# XTX.net
KiCad netlist of a schematic drawn in Altium Designer
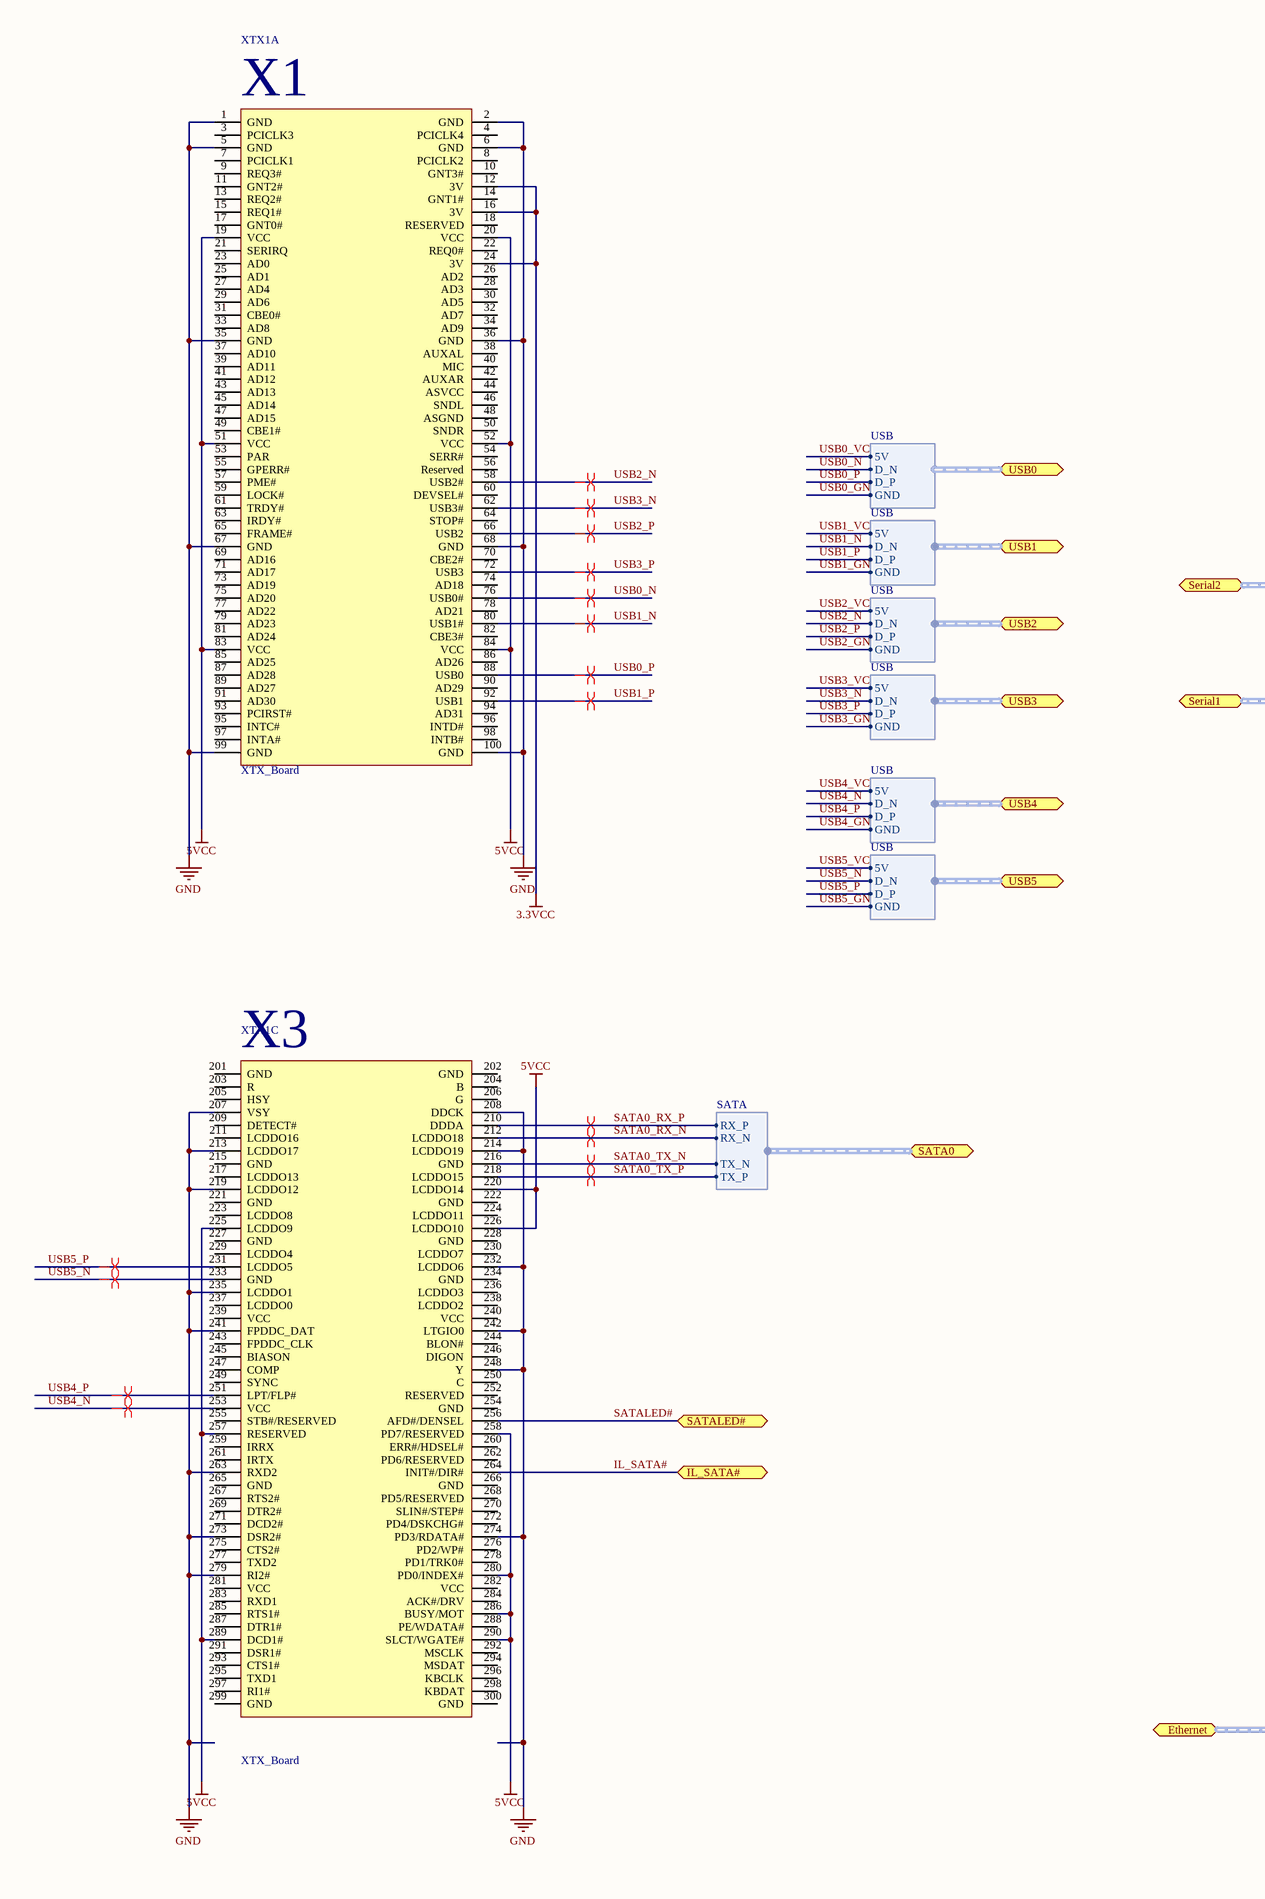
[diagram p0: XTX.SchDoc, left]
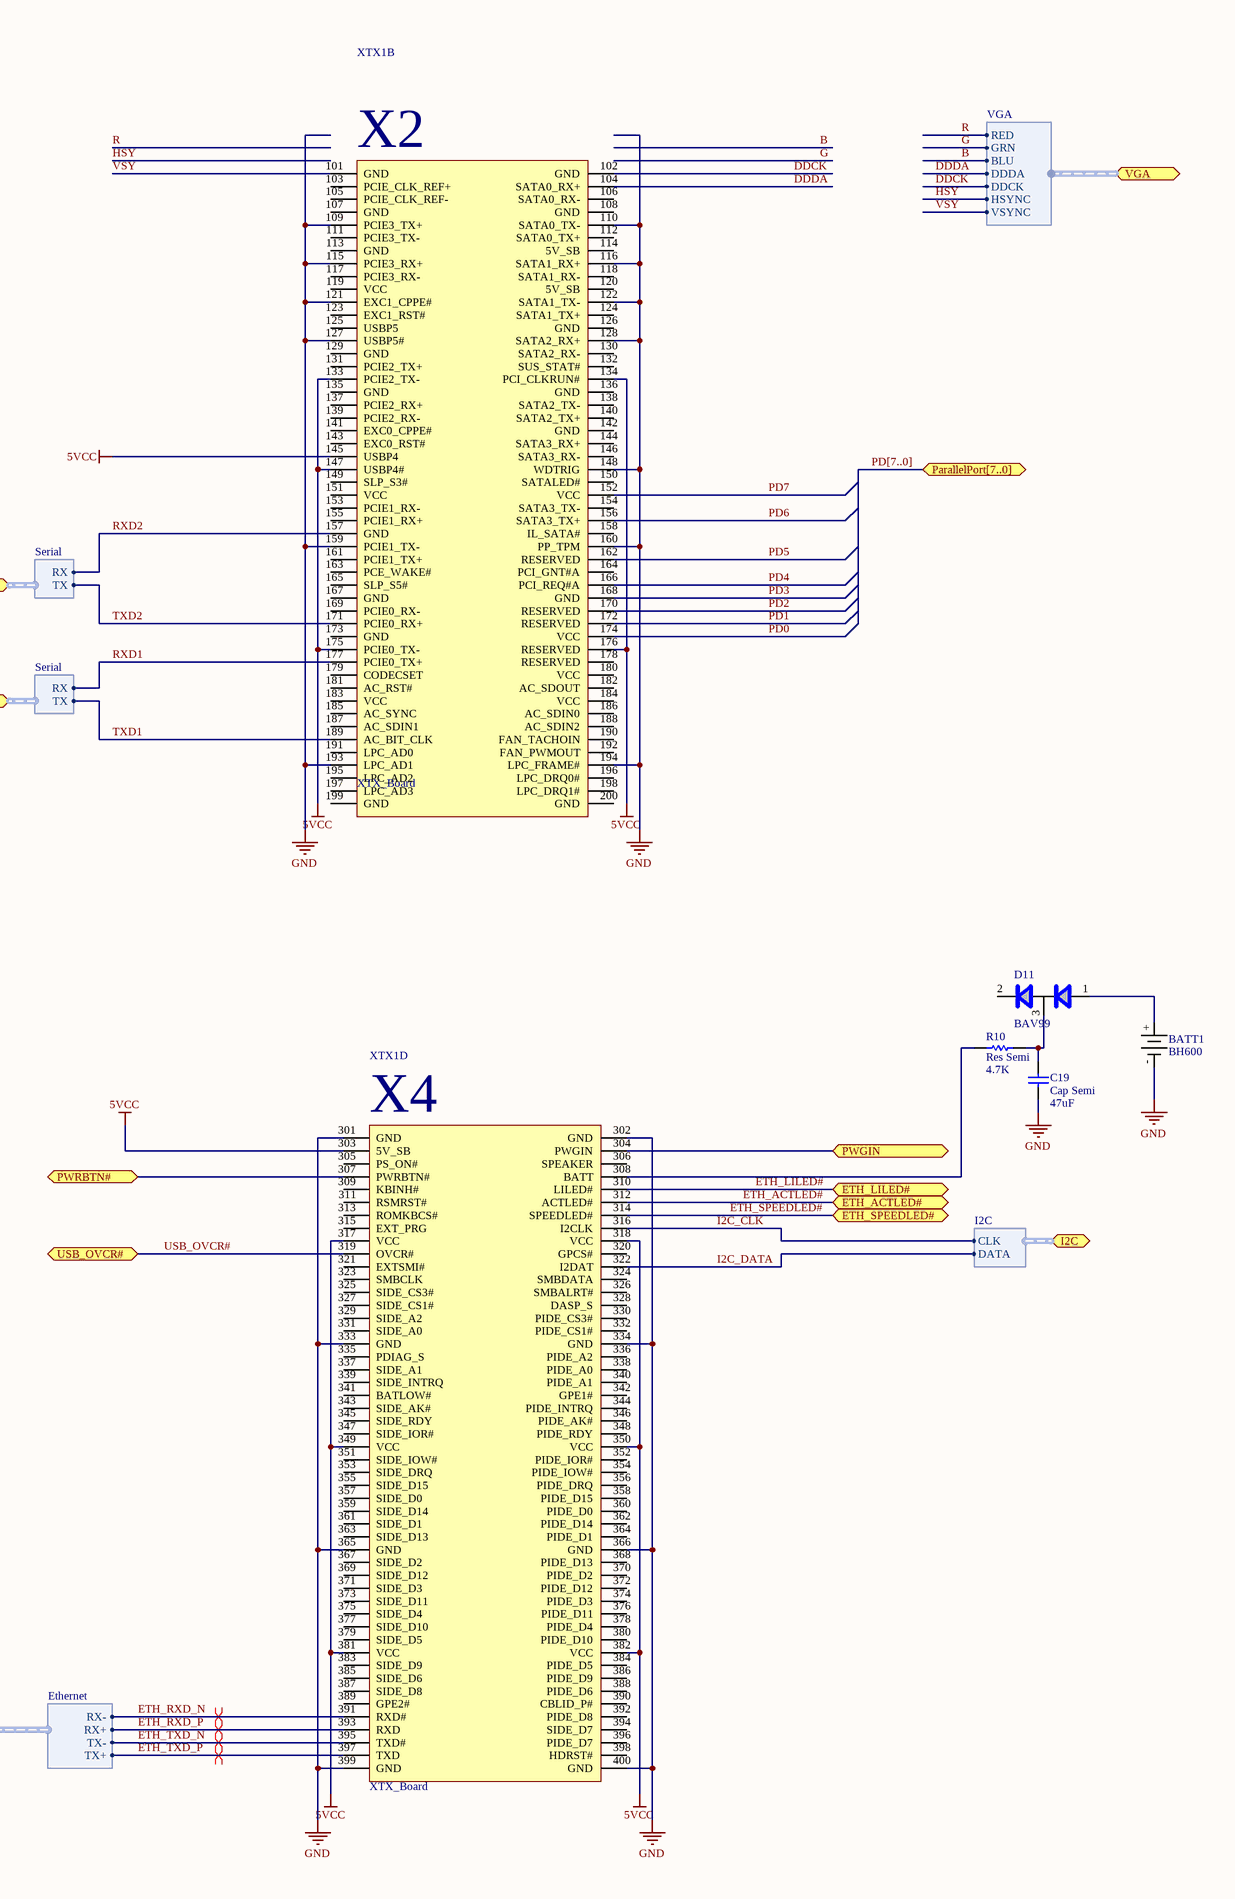
[diagram p1: XTX.SchDoc, right]

(export (version "E")
  (design (tool "Eeschema 10.0.6"))
  (components
    (comp (ref "BATT1")
      (value "BH600")
      (footprint "MemoryProtectionDevices:BH600")
      (description "16mm Battery Holder - Memory Protection Devices")
      (libsource (lib "CoinBatteryHolders") (part "BH600"))
    )
    (comp (ref "C19")
      (value "Cap Semi")
      (footprint "C1210")
      (description "Capacitor (Semiconductor SIM Model)")
      (fields (field (name "ALTIUM_VALUE") "47uF") (field (name "PUBLISHER") "Altium Limited"))
      (libsource (lib "Miscellaneous Devices") (part "Cap Semi"))
    )
    (comp (ref "D11")
      (value "BAV99")
      (footprint "SOT-23")
      (description "Dual Surface Mount Switching Diode")
      (fields (field (name "DIGIKEY PART NUMBER") "BAV99-FDICT-ND"))
      (libsource (lib "Diodes") (part "BAV99"))
    )
    (comp (ref "R10")
      (value "Res Semi")
      (footprint "1005[0402]")
      (description "Semiconductor Resistor")
      (fields (field (name "ALTIUM_VALUE") "4.7K") (field (name "PUBLISHER") "Altium Limited"))
      (libsource (lib "Miscellaneous Devices") (part "Res Semi"))
    )
    (comp (ref "XTX1") (value "XTX_Board") (footprint "XTX_Board") (libsource (lib "XTX") (part "XTX_Board")))
  )
  (nets
    (net (code "8") (name "/DDCK") (class "Default")
      (node (ref "XTX1") (pin "102") (pinfunction "GND_102") (pintype "passive"))
    )
    (net (code "9") (name "/DDDA") (class "Default")
      (node (ref "XTX1") (pin "104") (pinfunction "SATA0_RX+_104") (pintype "passive"))
    )
    (net (code "10") (name "/ETH_ACTLED#") (class "Default")
      (node (ref "XTX1") (pin "312") (pinfunction "ACTLED#_312") (pintype "passive"))
    )
    (net (code "11") (name "/ETH_LILED#") (class "Default")
      (node (ref "XTX1") (pin "310") (pinfunction "LILED#_310") (pintype "passive"))
    )
    (net (code "12") (name "/ETH_RXD_N") (class "Default")
      (node (ref "XTX1") (pin "391") (pinfunction "RXD#_391") (pintype "passive"))
    )
    (net (code "13") (name "/ETH_RXD_P") (class "Default")
      (node (ref "XTX1") (pin "393") (pinfunction "RXD_393") (pintype "passive"))
    )
    (net (code "14") (name "/ETH_SPEEDLED#") (class "Default")
      (node (ref "XTX1") (pin "314") (pinfunction "SPEEDLED#_314") (pintype "passive"))
    )
    (net (code "15") (name "/ETH_TXD_N") (class "Default")
      (node (ref "XTX1") (pin "395") (pinfunction "TXD#_395") (pintype "passive"))
    )
    (net (code "16") (name "/ETH_TXD_P") (class "Default")
      (node (ref "XTX1") (pin "397") (pinfunction "TXD_397") (pintype "passive"))
    )
    (net (code "19") (name "/I2C_CLK") (class "Default")
      (node (ref "XTX1") (pin "316") (pinfunction "I2CLK_316") (pintype "passive"))
    )
    (net (code "20") (name "/I2C_DATA") (class "Default")
      (node (ref "XTX1") (pin "322") (pinfunction "I2DAT_322") (pintype "passive"))
    )
    (net (code "21") (name "/IL_SATA#") (class "Default")
      (node (ref "XTX1") (pin "264") (pinfunction "INIT#/DIR#_264") (pintype "passive"))
    )
    (net (code "22") (name "/PD0") (class "Default")
      (node (ref "XTX1") (pin "174") (pinfunction "VCC_174") (pintype "passive"))
    )
    (net (code "23") (name "/PD1") (class "Default")
      (node (ref "XTX1") (pin "172") (pinfunction "RESERVED_172") (pintype "passive"))
    )
    (net (code "24") (name "/PD2") (class "Default")
      (node (ref "XTX1") (pin "170") (pinfunction "RESERVED_170") (pintype "passive"))
    )
    (net (code "25") (name "/PD3") (class "Default")
      (node (ref "XTX1") (pin "168") (pinfunction "GND_168") (pintype "passive"))
    )
    (net (code "26") (name "/PD4") (class "Default")
      (node (ref "XTX1") (pin "166") (pinfunction "PCI_REQ#A_166") (pintype "passive"))
    )
    (net (code "27") (name "/PD5") (class "Default")
      (node (ref "XTX1") (pin "162") (pinfunction "RESERVED_162") (pintype "passive"))
    )
    (net (code "28") (name "/PD6") (class "Default")
      (node (ref "XTX1") (pin "156") (pinfunction "SATA3_TX+_156") (pintype "passive"))
    )
    (net (code "29") (name "/PD7") (class "Default")
      (node (ref "XTX1") (pin "152") (pinfunction "VCC_152") (pintype "passive"))
    )
    (net (code "31") (name "/PWGIN") (class "Default")
      (node (ref "XTX1") (pin "304") (pinfunction "PWGIN_304") (pintype "passive"))
    )
    (net (code "32") (name "/PWRBTN#") (class "Default")
      (node (ref "XTX1") (pin "307") (pinfunction "PWRBTN#_307") (pintype "passive"))
    )
    (net (code "34") (name "/RXD1") (class "Default")
      (node (ref "XTX1") (pin "177") (pinfunction "PCIE0_TX+_177") (pintype "passive"))
    )
    (net (code "35") (name "/RXD2") (class "Default")
      (node (ref "XTX1") (pin "157") (pinfunction "GND_157") (pintype "passive"))
    )
    (net (code "36") (name "/SATA0_RX_N") (class "Default")
      (node (ref "XTX1") (pin "212") (pinfunction "LCDDO18_212") (pintype "passive"))
    )
    (net (code "37") (name "/SATA0_RX_P") (class "Default")
      (node (ref "XTX1") (pin "210") (pinfunction "DDDA_210") (pintype "passive"))
    )
    (net (code "38") (name "/SATA0_TX_N") (class "Default")
      (node (ref "XTX1") (pin "216") (pinfunction "GND_216") (pintype "passive"))
    )
    (net (code "39") (name "/SATA0_TX_P") (class "Default")
      (node (ref "XTX1") (pin "218") (pinfunction "LCDDO15_218") (pintype "passive"))
    )
    (net (code "40") (name "/SATALED#") (class "Default")
      (node (ref "XTX1") (pin "256") (pinfunction "AFD#/DENSEL_256") (pintype "passive"))
    )
    (net (code "41") (name "/TXD1") (class "Default")
      (node (ref "XTX1") (pin "189") (pinfunction "AC_BIT_CLK_189") (pintype "passive"))
    )
    (net (code "42") (name "/TXD2") (class "Default")
      (node (ref "XTX1") (pin "171") (pinfunction "PCIE0_RX+_171") (pintype "passive"))
    )
    (net (code "44") (name "/USB0_N") (class "Default")
      (node (ref "XTX1") (pin "76") (pinfunction "USB0#_76") (pintype "passive"))
    )
    (net (code "45") (name "/USB0_P") (class "Default")
      (node (ref "XTX1") (pin "88") (pinfunction "USB0_88") (pintype "passive"))
    )
    (net (code "48") (name "/USB1_N") (class "Default")
      (node (ref "XTX1") (pin "80") (pinfunction "USB1#_80") (pintype "passive"))
    )
    (net (code "49") (name "/USB1_P") (class "Default")
      (node (ref "XTX1") (pin "92") (pinfunction "USB1_92") (pintype "passive"))
    )
    (net (code "52") (name "/USB2_N") (class "Default")
      (node (ref "XTX1") (pin "58") (pinfunction "USB2#_58") (pintype "passive"))
    )
    (net (code "53") (name "/USB2_P") (class "Default")
      (node (ref "XTX1") (pin "66") (pinfunction "USB2_66") (pintype "passive"))
    )
    (net (code "56") (name "/USB3_N") (class "Default")
      (node (ref "XTX1") (pin "62") (pinfunction "USB3#_62") (pintype "passive"))
    )
    (net (code "57") (name "/USB3_P") (class "Default")
      (node (ref "XTX1") (pin "72") (pinfunction "USB3_72") (pintype "passive"))
    )
    (net (code "60") (name "/USB4_N") (class "Default")
      (node (ref "XTX1") (pin "253") (pinfunction "VCC_253") (pintype "passive"))
    )
    (net (code "61") (name "/USB4_P") (class "Default")
      (node (ref "XTX1") (pin "251") (pinfunction "LPT/FLP#_251") (pintype "passive"))
    )
    (net (code "64") (name "/USB5_N") (class "Default")
      (node (ref "XTX1") (pin "233") (pinfunction "GND_233") (pintype "passive"))
    )
    (net (code "65") (name "/USB5_P") (class "Default")
      (node (ref "XTX1") (pin "231") (pinfunction "LCDDO5_231") (pintype "passive"))
    )
    (net (code "67") (name "/USB_OVCR#") (class "Default")
      (node (ref "XTX1") (pin "319") (pinfunction "OVCR#_319") (pintype "passive"))
    )
    (net (code "68") (name "/VSY") (class "Default")
      (node (ref "XTX1") (pin "101") (pinfunction "GND_101") (pintype "passive"))
    )
    (net (code "75") (name "3.3VCC") (class "Default")
      (node (ref "XTX1") (pin "12") (pinfunction "3V_12") (pintype "passive"))
      (node (ref "XTX1") (pin "16") (pinfunction "3V_16") (pintype "passive"))
      (node (ref "XTX1") (pin "24") (pinfunction "3V_24") (pintype "passive"))
    )
    (net (code "76") (name "5VCC") (class "Default")
      (node (ref "XTX1") (pin "133") (pinfunction "PCIE2_TX-_133") (pintype "passive"))
      (node (ref "XTX1") (pin "134") (pinfunction "PCI_CLKRUN#_134") (pintype "passive"))
      (node (ref "XTX1") (pin "145") (pinfunction "USBP4_145") (pintype "passive"))
      (node (ref "XTX1") (pin "147") (pinfunction "USBP4#_147") (pintype "passive"))
      (node (ref "XTX1") (pin "175") (pinfunction "PCIE0_TX-_175") (pintype "passive"))
      (node (ref "XTX1") (pin "176") (pinfunction "RESERVED_176") (pintype "passive"))
      (node (ref "XTX1") (pin "19") (pinfunction "VCC_19") (pintype "passive"))
      (node (ref "XTX1") (pin "20") (pinfunction "VCC_20") (pintype "passive"))
      (node (ref "XTX1") (pin "220") (pinfunction "LCDDO14_220") (pintype "passive"))
      (node (ref "XTX1") (pin "225") (pinfunction "LCDDO9_225") (pintype "passive"))
      (node (ref "XTX1") (pin "226") (pinfunction "LCDDO10_226") (pintype "passive"))
      (node (ref "XTX1") (pin "257") (pinfunction "RESERVED_257") (pintype "passive"))
      (node (ref "XTX1") (pin "258") (pinfunction "PD7/RESERVED_258") (pintype "passive"))
      (node (ref "XTX1") (pin "280") (pinfunction "PD0/INDEX#_280") (pintype "passive"))
      (node (ref "XTX1") (pin "286") (pinfunction "BUSY/MOT_286") (pintype "passive"))
      (node (ref "XTX1") (pin "289") (pinfunction "DCD1#_289") (pintype "passive"))
      (node (ref "XTX1") (pin "290") (pinfunction "SLCT/WGATE#_290") (pintype "passive"))
      (node (ref "XTX1") (pin "303") (pinfunction "5V_SB_303") (pintype "passive"))
      (node (ref "XTX1") (pin "317") (pinfunction "VCC_317") (pintype "passive"))
      (node (ref "XTX1") (pin "318") (pinfunction "VCC_318") (pintype "passive"))
      (node (ref "XTX1") (pin "349") (pinfunction "VCC_349") (pintype "passive"))
      (node (ref "XTX1") (pin "350") (pinfunction "VCC_350") (pintype "passive"))
      (node (ref "XTX1") (pin "381") (pinfunction "VCC_381") (pintype "passive"))
      (node (ref "XTX1") (pin "382") (pinfunction "VCC_382") (pintype "passive"))
      (node (ref "XTX1") (pin "51") (pinfunction "VCC_51") (pintype "passive"))
      (node (ref "XTX1") (pin "52") (pinfunction "VCC_52") (pintype "passive"))
      (node (ref "XTX1") (pin "83") (pinfunction "VCC_83") (pintype "passive"))
      (node (ref "XTX1") (pin "84") (pinfunction "VCC_84") (pintype "passive"))
    )
    (net (code "77") (name "GND") (class "Default")
      (node (ref "BATT1") (pin "-") (pinfunction "1_-") (pintype "passive"))
      (node (ref "C19") (pin "1") (pinfunction "1_1") (pintype "passive"))
      (node (ref "XTX1") (pin "1") (pinfunction "GND_1") (pintype "passive"))
      (node (ref "XTX1") (pin "100") (pinfunction "GND_100") (pintype "passive"))
      (node (ref "XTX1") (pin "109") (pinfunction "PCIE3_TX+_109") (pintype "passive"))
      (node (ref "XTX1") (pin "110") (pinfunction "SATA0_TX-_110") (pintype "passive"))
      (node (ref "XTX1") (pin "115") (pinfunction "PCIE3_RX+_115") (pintype "passive"))
      (node (ref "XTX1") (pin "116") (pinfunction "SATA1_RX+_116") (pintype "passive"))
      (node (ref "XTX1") (pin "121") (pinfunction "EXC1_CPPE#_121") (pintype "passive"))
      (node (ref "XTX1") (pin "122") (pinfunction "SATA1_TX-_122") (pintype "passive"))
      (node (ref "XTX1") (pin "127") (pinfunction "USBP5#_127") (pintype "passive"))
      (node (ref "XTX1") (pin "128") (pinfunction "SATA2_RX+_128") (pintype "passive"))
      (node (ref "XTX1") (pin "148") (pinfunction "WDTRIG_148") (pintype "passive"))
      (node (ref "XTX1") (pin "159") (pinfunction "PCIE1_TX-_159") (pintype "passive"))
      (node (ref "XTX1") (pin "160") (pinfunction "PP_TPM_160") (pintype "passive"))
      (node (ref "XTX1") (pin "193") (pinfunction "LPC_AD1_193") (pintype "passive"))
      (node (ref "XTX1") (pin "194") (pinfunction "LPC_FRAME#_194") (pintype "passive"))
      (node (ref "XTX1") (pin "2") (pinfunction "GND_2") (pintype "passive"))
      (node (ref "XTX1") (pin "207") (pinfunction "VSY_207") (pintype "passive"))
      (node (ref "XTX1") (pin "208") (pinfunction "DDCK_208") (pintype "passive"))
      (node (ref "XTX1") (pin "213") (pinfunction "LCDDO17_213") (pintype "passive"))
      (node (ref "XTX1") (pin "214") (pinfunction "LCDDO19_214") (pintype "passive"))
      (node (ref "XTX1") (pin "219") (pinfunction "LCDDO12_219") (pintype "passive"))
      (node (ref "XTX1") (pin "232") (pinfunction "LCDDO6_232") (pintype "passive"))
      (node (ref "XTX1") (pin "235") (pinfunction "LCDDO1_235") (pintype "passive"))
      (node (ref "XTX1") (pin "241") (pinfunction "FPDDC_DAT_241") (pintype "passive"))
      (node (ref "XTX1") (pin "242") (pinfunction "LTGIO0_242") (pintype "passive"))
      (node (ref "XTX1") (pin "248") (pinfunction "Y_248") (pintype "passive"))
      (node (ref "XTX1") (pin "263") (pinfunction "RXD2_263") (pintype "passive"))
      (node (ref "XTX1") (pin "273") (pinfunction "DSR2#_273") (pintype "passive"))
      (node (ref "XTX1") (pin "274") (pinfunction "PD3/RDATA#_274") (pintype "passive"))
      (node (ref "XTX1") (pin "279") (pinfunction "RI2#_279") (pintype "passive"))
      (node (ref "XTX1") (pin "301") (pinfunction "GND_301") (pintype "passive"))
      (node (ref "XTX1") (pin "302") (pinfunction "GND_302") (pintype "passive"))
      (node (ref "XTX1") (pin "333") (pinfunction "GND_333") (pintype "passive"))
      (node (ref "XTX1") (pin "334") (pinfunction "GND_334") (pintype "passive"))
      (node (ref "XTX1") (pin "35") (pinfunction "GND_35") (pintype "passive"))
      (node (ref "XTX1") (pin "36") (pinfunction "GND_36") (pintype "passive"))
      (node (ref "XTX1") (pin "365") (pinfunction "GND_365") (pintype "passive"))
      (node (ref "XTX1") (pin "366") (pinfunction "GND_366") (pintype "passive"))
      (node (ref "XTX1") (pin "399") (pinfunction "GND_399") (pintype "passive"))
      (node (ref "XTX1") (pin "400") (pinfunction "GND_400") (pintype "passive"))
      (node (ref "XTX1") (pin "5") (pinfunction "GND_5") (pintype "passive"))
      (node (ref "XTX1") (pin "6") (pinfunction "GND_6") (pintype "passive"))
      (node (ref "XTX1") (pin "67") (pinfunction "GND_67") (pintype "passive"))
      (node (ref "XTX1") (pin "68") (pinfunction "GND_68") (pintype "passive"))
      (node (ref "XTX1") (pin "99") (pinfunction "GND_99") (pintype "passive"))
    )
    (net (code "78") (name "Net-(BATT1-0)") (class "Default")
      (node (ref "BATT1") (pin "+") (pinfunction "0_+") (pintype "passive"))
      (node (ref "D11") (pin "1") (pinfunction "1_1") (pintype "passive"))
    )
    (net (code "79") (name "Net-(C19-Pad2)") (class "Default")
      (node (ref "C19") (pin "2") (pinfunction "2_2") (pintype "passive"))
      (node (ref "D11") (pin "3") (pinfunction "3_3") (pintype "passive"))
      (node (ref "R10") (pin "2") (pinfunction "2_2") (pintype "passive"))
    )
    (net (code "80") (name "Net-(XTX1D-BATT)") (class "Default")
      (node (ref "R10") (pin "1") (pinfunction "1_1") (pintype "passive"))
      (node (ref "XTX1") (pin "308") (pinfunction "BATT_308") (pintype "passive"))
    )
    (net (code "81") (name "unconnected-(D11-Pad2)") (class "Default")
      (node (ref "D11") (pin "2") (pinfunction "2_2") (pintype "passive"))
    )
    (net (code "82") (name "unconnected-(XTX1A-AD0-Pad23)") (class "Default")
      (node (ref "XTX1") (pin "23") (pinfunction "AD0_23") (pintype "passive"))
    )
    (net (code "83") (name "unconnected-(XTX1A-AD1-Pad25)") (class "Default")
      (node (ref "XTX1") (pin "25") (pinfunction "AD1_25") (pintype "passive"))
    )
    (net (code "84") (name "unconnected-(XTX1A-AD2-Pad26)") (class "Default")
      (node (ref "XTX1") (pin "26") (pinfunction "AD2_26") (pintype "passive"))
    )
    (net (code "85") (name "unconnected-(XTX1A-AD3-Pad28)") (class "Default")
      (node (ref "XTX1") (pin "28") (pinfunction "AD3_28") (pintype "passive"))
    )
    (net (code "86") (name "unconnected-(XTX1A-AD4-Pad27)") (class "Default")
      (node (ref "XTX1") (pin "27") (pinfunction "AD4_27") (pintype "passive"))
    )
    (net (code "87") (name "unconnected-(XTX1A-AD5-Pad30)") (class "Default")
      (node (ref "XTX1") (pin "30") (pinfunction "AD5_30") (pintype "passive"))
    )
    (net (code "88") (name "unconnected-(XTX1A-AD6-Pad29)") (class "Default")
      (node (ref "XTX1") (pin "29") (pinfunction "AD6_29") (pintype "passive"))
    )
    (net (code "89") (name "unconnected-(XTX1A-AD7-Pad32)") (class "Default")
      (node (ref "XTX1") (pin "32") (pinfunction "AD7_32") (pintype "passive"))
    )
    (net (code "90") (name "unconnected-(XTX1A-AD8-Pad33)") (class "Default")
      (node (ref "XTX1") (pin "33") (pinfunction "AD8_33") (pintype "passive"))
    )
    (net (code "91") (name "unconnected-(XTX1A-AD9-Pad34)") (class "Default")
      (node (ref "XTX1") (pin "34") (pinfunction "AD9_34") (pintype "passive"))
    )
    (net (code "92") (name "unconnected-(XTX1A-AD10-Pad37)") (class "Default")
      (node (ref "XTX1") (pin "37") (pinfunction "AD10_37") (pintype "passive"))
    )
    (net (code "93") (name "unconnected-(XTX1A-AD11-Pad39)") (class "Default")
      (node (ref "XTX1") (pin "39") (pinfunction "AD11_39") (pintype "passive"))
    )
    (net (code "94") (name "unconnected-(XTX1A-AD12-Pad41)") (class "Default")
      (node (ref "XTX1") (pin "41") (pinfunction "AD12_41") (pintype "passive"))
    )
    (net (code "95") (name "unconnected-(XTX1A-AD13-Pad43)") (class "Default")
      (node (ref "XTX1") (pin "43") (pinfunction "AD13_43") (pintype "passive"))
    )
    (net (code "96") (name "unconnected-(XTX1A-AD14-Pad45)") (class "Default")
      (node (ref "XTX1") (pin "45") (pinfunction "AD14_45") (pintype "passive"))
    )
    (net (code "97") (name "unconnected-(XTX1A-AD15-Pad47)") (class "Default")
      (node (ref "XTX1") (pin "47") (pinfunction "AD15_47") (pintype "passive"))
    )
    (net (code "98") (name "unconnected-(XTX1A-AD16-Pad69)") (class "Default")
      (node (ref "XTX1") (pin "69") (pinfunction "AD16_69") (pintype "passive"))
    )
    (net (code "99") (name "unconnected-(XTX1A-AD17-Pad71)") (class "Default")
      (node (ref "XTX1") (pin "71") (pinfunction "AD17_71") (pintype "passive"))
    )
    (net (code "100") (name "unconnected-(XTX1A-AD18-Pad74)") (class "Default")
      (node (ref "XTX1") (pin "74") (pinfunction "AD18_74") (pintype "passive"))
    )
    (net (code "101") (name "unconnected-(XTX1A-AD19-Pad73)") (class "Default")
      (node (ref "XTX1") (pin "73") (pinfunction "AD19_73") (pintype "passive"))
    )
    (net (code "102") (name "unconnected-(XTX1A-AD20-Pad75)") (class "Default")
      (node (ref "XTX1") (pin "75") (pinfunction "AD20_75") (pintype "passive"))
    )
    (net (code "103") (name "unconnected-(XTX1A-AD21-Pad78)") (class "Default")
      (node (ref "XTX1") (pin "78") (pinfunction "AD21_78") (pintype "passive"))
    )
    (net (code "104") (name "unconnected-(XTX1A-AD22-Pad77)") (class "Default")
      (node (ref "XTX1") (pin "77") (pinfunction "AD22_77") (pintype "passive"))
    )
    (net (code "105") (name "unconnected-(XTX1A-AD23-Pad79)") (class "Default")
      (node (ref "XTX1") (pin "79") (pinfunction "AD23_79") (pintype "passive"))
    )
    (net (code "106") (name "unconnected-(XTX1A-AD24-Pad81)") (class "Default")
      (node (ref "XTX1") (pin "81") (pinfunction "AD24_81") (pintype "passive"))
    )
    (net (code "107") (name "unconnected-(XTX1A-AD25-Pad85)") (class "Default")
      (node (ref "XTX1") (pin "85") (pinfunction "AD25_85") (pintype "passive"))
    )
    (net (code "108") (name "unconnected-(XTX1A-AD26-Pad86)") (class "Default")
      (node (ref "XTX1") (pin "86") (pinfunction "AD26_86") (pintype "passive"))
    )
    (net (code "109") (name "unconnected-(XTX1A-AD27-Pad89)") (class "Default")
      (node (ref "XTX1") (pin "89") (pinfunction "AD27_89") (pintype "passive"))
    )
    (net (code "110") (name "unconnected-(XTX1A-AD28-Pad87)") (class "Default")
      (node (ref "XTX1") (pin "87") (pinfunction "AD28_87") (pintype "passive"))
    )
    (net (code "111") (name "unconnected-(XTX1A-AD29-Pad90)") (class "Default")
      (node (ref "XTX1") (pin "90") (pinfunction "AD29_90") (pintype "passive"))
    )
    (net (code "112") (name "unconnected-(XTX1A-AD30-Pad91)") (class "Default")
      (node (ref "XTX1") (pin "91") (pinfunction "AD30_91") (pintype "passive"))
    )
    (net (code "113") (name "unconnected-(XTX1A-AD31-Pad94)") (class "Default")
      (node (ref "XTX1") (pin "94") (pinfunction "AD31_94") (pintype "passive"))
    )
    (net (code "114") (name "unconnected-(XTX1A-ASGND-Pad48)") (class "Default")
      (node (ref "XTX1") (pin "48") (pinfunction "ASGND_48") (pintype "passive"))
    )
    (net (code "115") (name "unconnected-(XTX1A-ASVCC-Pad44)") (class "Default")
      (node (ref "XTX1") (pin "44") (pinfunction "ASVCC_44") (pintype "passive"))
    )
    (net (code "116") (name "unconnected-(XTX1A-AUXAL-Pad38)") (class "Default")
      (node (ref "XTX1") (pin "38") (pinfunction "AUXAL_38") (pintype "passive"))
    )
    (net (code "117") (name "unconnected-(XTX1A-AUXAR-Pad42)") (class "Default")
      (node (ref "XTX1") (pin "42") (pinfunction "AUXAR_42") (pintype "passive"))
    )
    (net (code "118") (name "unconnected-(XTX1A-CBE0#-Pad31)") (class "Default")
      (node (ref "XTX1") (pin "31") (pinfunction "CBE0#_31") (pintype "passive"))
    )
    (net (code "119") (name "unconnected-(XTX1A-CBE1#-Pad49)") (class "Default")
      (node (ref "XTX1") (pin "49") (pinfunction "CBE1#_49") (pintype "passive"))
    )
    (net (code "120") (name "unconnected-(XTX1A-CBE2#-Pad70)") (class "Default")
      (node (ref "XTX1") (pin "70") (pinfunction "CBE2#_70") (pintype "passive"))
    )
    (net (code "121") (name "unconnected-(XTX1A-CBE3#-Pad82)") (class "Default")
      (node (ref "XTX1") (pin "82") (pinfunction "CBE3#_82") (pintype "passive"))
    )
    (net (code "122") (name "unconnected-(XTX1A-DEVSEL#-Pad60)") (class "Default")
      (node (ref "XTX1") (pin "60") (pinfunction "DEVSEL#_60") (pintype "passive"))
    )
    (net (code "123") (name "unconnected-(XTX1A-FRAME#-Pad65)") (class "Default")
      (node (ref "XTX1") (pin "65") (pinfunction "FRAME#_65") (pintype "passive"))
    )
    (net (code "124") (name "unconnected-(XTX1A-GNT0#-Pad17)") (class "Default")
      (node (ref "XTX1") (pin "17") (pinfunction "GNT0#_17") (pintype "passive"))
    )
    (net (code "125") (name "unconnected-(XTX1A-GNT1#-Pad14)") (class "Default")
      (node (ref "XTX1") (pin "14") (pinfunction "GNT1#_14") (pintype "passive"))
    )
    (net (code "126") (name "unconnected-(XTX1A-GNT2#-Pad11)") (class "Default")
      (node (ref "XTX1") (pin "11") (pinfunction "GNT2#_11") (pintype "passive"))
    )
    (net (code "127") (name "unconnected-(XTX1A-GNT3#-Pad10)") (class "Default")
      (node (ref "XTX1") (pin "10") (pinfunction "GNT3#_10") (pintype "passive"))
    )
    (net (code "128") (name "unconnected-(XTX1A-GPERR#-Pad55)") (class "Default")
      (node (ref "XTX1") (pin "55") (pinfunction "GPERR#_55") (pintype "passive"))
    )
    (net (code "129") (name "unconnected-(XTX1A-INTA#-Pad97)") (class "Default")
      (node (ref "XTX1") (pin "97") (pinfunction "INTA#_97") (pintype "passive"))
    )
    (net (code "130") (name "unconnected-(XTX1A-INTB#-Pad98)") (class "Default")
      (node (ref "XTX1") (pin "98") (pinfunction "INTB#_98") (pintype "passive"))
    )
    (net (code "131") (name "unconnected-(XTX1A-INTC#-Pad95)") (class "Default")
      (node (ref "XTX1") (pin "95") (pinfunction "INTC#_95") (pintype "passive"))
    )
    (net (code "132") (name "unconnected-(XTX1A-INTD#-Pad96)") (class "Default")
      (node (ref "XTX1") (pin "96") (pinfunction "INTD#_96") (pintype "passive"))
    )
    (net (code "133") (name "unconnected-(XTX1A-IRDY#-Pad63)") (class "Default")
      (node (ref "XTX1") (pin "63") (pinfunction "IRDY#_63") (pintype "passive"))
    )
    (net (code "134") (name "unconnected-(XTX1A-LOCK#-Pad59)") (class "Default")
      (node (ref "XTX1") (pin "59") (pinfunction "LOCK#_59") (pintype "passive"))
    )
    (net (code "135") (name "unconnected-(XTX1A-MIC-Pad40)") (class "Default")
      (node (ref "XTX1") (pin "40") (pinfunction "MIC_40") (pintype "passive"))
    )
    (net (code "136") (name "unconnected-(XTX1A-PAR-Pad53)") (class "Default")
      (node (ref "XTX1") (pin "53") (pinfunction "PAR_53") (pintype "passive"))
    )
    (net (code "137") (name "unconnected-(XTX1A-PCICLK1-Pad7)") (class "Default")
      (node (ref "XTX1") (pin "7") (pinfunction "PCICLK1_7") (pintype "passive"))
    )
    (net (code "138") (name "unconnected-(XTX1A-PCICLK2-Pad8)") (class "Default")
      (node (ref "XTX1") (pin "8") (pinfunction "PCICLK2_8") (pintype "passive"))
    )
    (net (code "139") (name "unconnected-(XTX1A-PCICLK3-Pad3)") (class "Default")
      (node (ref "XTX1") (pin "3") (pinfunction "PCICLK3_3") (pintype "passive"))
    )
    (net (code "140") (name "unconnected-(XTX1A-PCICLK4-Pad4)") (class "Default")
      (node (ref "XTX1") (pin "4") (pinfunction "PCICLK4_4") (pintype "passive"))
    )
    (net (code "141") (name "unconnected-(XTX1A-PCIRST#-Pad93)") (class "Default")
      (node (ref "XTX1") (pin "93") (pinfunction "PCIRST#_93") (pintype "passive"))
    )
    (net (code "142") (name "unconnected-(XTX1A-PME#-Pad57)") (class "Default")
      (node (ref "XTX1") (pin "57") (pinfunction "PME#_57") (pintype "passive"))
    )
    (net (code "143") (name "unconnected-(XTX1A-REQ0#-Pad22)") (class "Default")
      (node (ref "XTX1") (pin "22") (pinfunction "REQ0#_22") (pintype "passive"))
    )
    (net (code "144") (name "unconnected-(XTX1A-REQ1#-Pad15)") (class "Default")
      (node (ref "XTX1") (pin "15") (pinfunction "REQ1#_15") (pintype "passive"))
    )
    (net (code "145") (name "unconnected-(XTX1A-REQ2#-Pad13)") (class "Default")
      (node (ref "XTX1") (pin "13") (pinfunction "REQ2#_13") (pintype "passive"))
    )
    (net (code "146") (name "unconnected-(XTX1A-REQ3#-Pad9)") (class "Default")
      (node (ref "XTX1") (pin "9") (pinfunction "REQ3#_9") (pintype "passive"))
    )
    (net (code "147") (name "unconnected-(XTX1A-RESERVED-Pad18)") (class "Default")
      (node (ref "XTX1") (pin "18") (pinfunction "RESERVED_18") (pintype "passive"))
    )
    (net (code "148") (name "unconnected-(XTX1A-Reserved-Pad56)") (class "Default")
      (node (ref "XTX1") (pin "56") (pinfunction "Reserved_56") (pintype "passive"))
    )
    (net (code "149") (name "unconnected-(XTX1A-SERIRQ-Pad21)") (class "Default")
      (node (ref "XTX1") (pin "21") (pinfunction "SERIRQ_21") (pintype "passive"))
    )
    (net (code "150") (name "unconnected-(XTX1A-SERR#-Pad54)") (class "Default")
      (node (ref "XTX1") (pin "54") (pinfunction "SERR#_54") (pintype "passive"))
    )
    (net (code "151") (name "unconnected-(XTX1A-SNDL-Pad46)") (class "Default")
      (node (ref "XTX1") (pin "46") (pinfunction "SNDL_46") (pintype "passive"))
    )
    (net (code "152") (name "unconnected-(XTX1A-SNDR-Pad50)") (class "Default")
      (node (ref "XTX1") (pin "50") (pinfunction "SNDR_50") (pintype "passive"))
    )
    (net (code "153") (name "unconnected-(XTX1A-STOP#-Pad64)") (class "Default")
      (node (ref "XTX1") (pin "64") (pinfunction "STOP#_64") (pintype "passive"))
    )
    (net (code "154") (name "unconnected-(XTX1A-TRDY#-Pad61)") (class "Default")
      (node (ref "XTX1") (pin "61") (pinfunction "TRDY#_61") (pintype "passive"))
    )
    (net (code "155") (name "unconnected-(XTX1B-5V_SB-Pad114)") (class "Default")
      (node (ref "XTX1") (pin "114") (pinfunction "5V_SB_114") (pintype "passive"))
    )
    (net (code "156") (name "unconnected-(XTX1B-5V_SB-Pad120)") (class "Default")
      (node (ref "XTX1") (pin "120") (pinfunction "5V_SB_120") (pintype "passive"))
    )
    (net (code "157") (name "unconnected-(XTX1B-AC_RST#-Pad181)") (class "Default")
      (node (ref "XTX1") (pin "181") (pinfunction "AC_RST#_181") (pintype "passive"))
    )
    (net (code "158") (name "unconnected-(XTX1B-AC_SDIN0-Pad186)") (class "Default")
      (node (ref "XTX1") (pin "186") (pinfunction "AC_SDIN0_186") (pintype "passive"))
    )
    (net (code "159") (name "unconnected-(XTX1B-AC_SDIN1-Pad187)") (class "Default")
      (node (ref "XTX1") (pin "187") (pinfunction "AC_SDIN1_187") (pintype "passive"))
    )
    (net (code "160") (name "unconnected-(XTX1B-AC_SDIN2-Pad188)") (class "Default")
      (node (ref "XTX1") (pin "188") (pinfunction "AC_SDIN2_188") (pintype "passive"))
    )
    (net (code "161") (name "unconnected-(XTX1B-AC_SDOUT-Pad182)") (class "Default")
      (node (ref "XTX1") (pin "182") (pinfunction "AC_SDOUT_182") (pintype "passive"))
    )
    (net (code "162") (name "unconnected-(XTX1B-AC_SYNC-Pad185)") (class "Default")
      (node (ref "XTX1") (pin "185") (pinfunction "AC_SYNC_185") (pintype "passive"))
    )
    (net (code "163") (name "unconnected-(XTX1B-CODECSET-Pad179)") (class "Default")
      (node (ref "XTX1") (pin "179") (pinfunction "CODECSET_179") (pintype "passive"))
    )
    (net (code "164") (name "unconnected-(XTX1B-EXC0_CPPE#-Pad141)") (class "Default")
      (node (ref "XTX1") (pin "141") (pinfunction "EXC0_CPPE#_141") (pintype "passive"))
    )
    (net (code "165") (name "unconnected-(XTX1B-EXC0_RST#-Pad143)") (class "Default")
      (node (ref "XTX1") (pin "143") (pinfunction "EXC0_RST#_143") (pintype "passive"))
    )
    (net (code "166") (name "unconnected-(XTX1B-EXC1_RST#-Pad123)") (class "Default")
      (node (ref "XTX1") (pin "123") (pinfunction "EXC1_RST#_123") (pintype "passive"))
    )
    (net (code "167") (name "unconnected-(XTX1B-FAN_PWMOUT-Pad192)") (class "Default")
      (node (ref "XTX1") (pin "192") (pinfunction "FAN_PWMOUT_192") (pintype "passive"))
    )
    (net (code "168") (name "unconnected-(XTX1B-FAN_TACHOIN-Pad190)") (class "Default")
      (node (ref "XTX1") (pin "190") (pinfunction "FAN_TACHOIN_190") (pintype "passive"))
    )
    (net (code "169") (name "unconnected-(XTX1B-GND-Pad107)") (class "Default")
      (node (ref "XTX1") (pin "107") (pinfunction "GND_107") (pintype "passive"))
    )
    (net (code "170") (name "unconnected-(XTX1B-GND-Pad108)") (class "Default")
      (node (ref "XTX1") (pin "108") (pinfunction "GND_108") (pintype "passive"))
    )
    (net (code "171") (name "unconnected-(XTX1B-GND-Pad113)") (class "Default")
      (node (ref "XTX1") (pin "113") (pinfunction "GND_113") (pintype "passive"))
    )
    (net (code "172") (name "unconnected-(XTX1B-GND-Pad126)") (class "Default")
      (node (ref "XTX1") (pin "126") (pinfunction "GND_126") (pintype "passive"))
    )
    (net (code "173") (name "unconnected-(XTX1B-GND-Pad129)") (class "Default")
      (node (ref "XTX1") (pin "129") (pinfunction "GND_129") (pintype "passive"))
    )
    (net (code "174") (name "unconnected-(XTX1B-GND-Pad135)") (class "Default")
      (node (ref "XTX1") (pin "135") (pinfunction "GND_135") (pintype "passive"))
    )
    (net (code "175") (name "unconnected-(XTX1B-GND-Pad136)") (class "Default")
      (node (ref "XTX1") (pin "136") (pinfunction "GND_136") (pintype "passive"))
    )
    (net (code "176") (name "unconnected-(XTX1B-GND-Pad142)") (class "Default")
      (node (ref "XTX1") (pin "142") (pinfunction "GND_142") (pintype "passive"))
    )
    (net (code "177") (name "unconnected-(XTX1B-GND-Pad167)") (class "Default")
      (node (ref "XTX1") (pin "167") (pinfunction "GND_167") (pintype "passive"))
    )
    (net (code "178") (name "unconnected-(XTX1B-GND-Pad173)") (class "Default")
      (node (ref "XTX1") (pin "173") (pinfunction "GND_173") (pintype "passive"))
    )
    (net (code "179") (name "unconnected-(XTX1B-GND-Pad199)") (class "Default")
      (node (ref "XTX1") (pin "199") (pinfunction "GND_199") (pintype "passive"))
    )
    (net (code "180") (name "unconnected-(XTX1B-GND-Pad200)") (class "Default")
      (node (ref "XTX1") (pin "200") (pinfunction "GND_200") (pintype "passive"))
    )
    (net (code "181") (name "unconnected-(XTX1B-IL_SATA#-Pad158)") (class "Default")
      (node (ref "XTX1") (pin "158") (pinfunction "IL_SATA#_158") (pintype "passive"))
    )
    (net (code "182") (name "unconnected-(XTX1B-LPC_AD0-Pad191)") (class "Default")
      (node (ref "XTX1") (pin "191") (pinfunction "LPC_AD0_191") (pintype "passive"))
    )
    (net (code "183") (name "unconnected-(XTX1B-LPC_AD2-Pad195)") (class "Default")
      (node (ref "XTX1") (pin "195") (pinfunction "LPC_AD2_195") (pintype "passive"))
    )
    (net (code "184") (name "unconnected-(XTX1B-LPC_AD3-Pad197)") (class "Default")
      (node (ref "XTX1") (pin "197") (pinfunction "LPC_AD3_197") (pintype "passive"))
    )
    (net (code "185") (name "unconnected-(XTX1B-LPC_DRQ0#-Pad196)") (class "Default")
      (node (ref "XTX1") (pin "196") (pinfunction "LPC_DRQ0#_196") (pintype "passive"))
    )
    (net (code "186") (name "unconnected-(XTX1B-LPC_DRQ1#-Pad198)") (class "Default")
      (node (ref "XTX1") (pin "198") (pinfunction "LPC_DRQ1#_198") (pintype "passive"))
    )
    (net (code "187") (name "unconnected-(XTX1B-PCE_WAKE#-Pad163)") (class "Default")
      (node (ref "XTX1") (pin "163") (pinfunction "PCE_WAKE#_163") (pintype "passive"))
    )
    (net (code "188") (name "unconnected-(XTX1B-PCIE0_RX--Pad169)") (class "Default")
      (node (ref "XTX1") (pin "169") (pinfunction "PCIE0_RX-_169") (pintype "passive"))
    )
    (net (code "189") (name "unconnected-(XTX1B-PCIE1_RX+-Pad155)") (class "Default")
      (node (ref "XTX1") (pin "155") (pinfunction "PCIE1_RX+_155") (pintype "passive"))
    )
    (net (code "190") (name "unconnected-(XTX1B-PCIE1_RX--Pad153)") (class "Default")
      (node (ref "XTX1") (pin "153") (pinfunction "PCIE1_RX-_153") (pintype "passive"))
    )
    (net (code "191") (name "unconnected-(XTX1B-PCIE1_TX+-Pad161)") (class "Default")
      (node (ref "XTX1") (pin "161") (pinfunction "PCIE1_TX+_161") (pintype "passive"))
    )
    (net (code "192") (name "unconnected-(XTX1B-PCIE2_RX+-Pad137)") (class "Default")
      (node (ref "XTX1") (pin "137") (pinfunction "PCIE2_RX+_137") (pintype "passive"))
    )
    (net (code "193") (name "unconnected-(XTX1B-PCIE2_RX--Pad139)") (class "Default")
      (node (ref "XTX1") (pin "139") (pinfunction "PCIE2_RX-_139") (pintype "passive"))
    )
    (net (code "194") (name "unconnected-(XTX1B-PCIE2_TX+-Pad131)") (class "Default")
      (node (ref "XTX1") (pin "131") (pinfunction "PCIE2_TX+_131") (pintype "passive"))
    )
    (net (code "195") (name "unconnected-(XTX1B-PCIE3_RX--Pad117)") (class "Default")
      (node (ref "XTX1") (pin "117") (pinfunction "PCIE3_RX-_117") (pintype "passive"))
    )
    (net (code "196") (name "unconnected-(XTX1B-PCIE3_TX--Pad111)") (class "Default")
      (node (ref "XTX1") (pin "111") (pinfunction "PCIE3_TX-_111") (pintype "passive"))
    )
    (net (code "197") (name "unconnected-(XTX1B-PCIE_CLK_REF+-Pad103)") (class "Default")
      (node (ref "XTX1") (pin "103") (pinfunction "PCIE_CLK_REF+_103") (pintype "passive"))
    )
    (net (code "198") (name "unconnected-(XTX1B-PCIE_CLK_REF--Pad105)") (class "Default")
      (node (ref "XTX1") (pin "105") (pinfunction "PCIE_CLK_REF-_105") (pintype "passive"))
    )
    (net (code "199") (name "unconnected-(XTX1B-PCI_GNT#A-Pad164)") (class "Default")
      (node (ref "XTX1") (pin "164") (pinfunction "PCI_GNT#A_164") (pintype "passive"))
    )
    (net (code "200") (name "unconnected-(XTX1B-RESERVED-Pad178)") (class "Default")
      (node (ref "XTX1") (pin "178") (pinfunction "RESERVED_178") (pintype "passive"))
    )
    (net (code "201") (name "unconnected-(XTX1B-SATA0_RX--Pad106)") (class "Default")
      (node (ref "XTX1") (pin "106") (pinfunction "SATA0_RX-_106") (pintype "passive"))
    )
    (net (code "202") (name "unconnected-(XTX1B-SATA0_TX+-Pad112)") (class "Default")
      (node (ref "XTX1") (pin "112") (pinfunction "SATA0_TX+_112") (pintype "passive"))
    )
    (net (code "203") (name "unconnected-(XTX1B-SATA1_RX--Pad118)") (class "Default")
      (node (ref "XTX1") (pin "118") (pinfunction "SATA1_RX-_118") (pintype "passive"))
    )
    (net (code "204") (name "unconnected-(XTX1B-SATA1_TX+-Pad124)") (class "Default")
      (node (ref "XTX1") (pin "124") (pinfunction "SATA1_TX+_124") (pintype "passive"))
    )
    (net (code "205") (name "unconnected-(XTX1B-SATA2_RX--Pad130)") (class "Default")
      (node (ref "XTX1") (pin "130") (pinfunction "SATA2_RX-_130") (pintype "passive"))
    )
    (net (code "206") (name "unconnected-(XTX1B-SATA2_TX+-Pad140)") (class "Default")
      (node (ref "XTX1") (pin "140") (pinfunction "SATA2_TX+_140") (pintype "passive"))
    )
    (net (code "207") (name "unconnected-(XTX1B-SATA2_TX--Pad138)") (class "Default")
      (node (ref "XTX1") (pin "138") (pinfunction "SATA2_TX-_138") (pintype "passive"))
    )
    (net (code "208") (name "unconnected-(XTX1B-SATA3_RX+-Pad144)") (class "Default")
      (node (ref "XTX1") (pin "144") (pinfunction "SATA3_RX+_144") (pintype "passive"))
    )
    (net (code "209") (name "unconnected-(XTX1B-SATA3_RX--Pad146)") (class "Default")
      (node (ref "XTX1") (pin "146") (pinfunction "SATA3_RX-_146") (pintype "passive"))
    )
    (net (code "210") (name "unconnected-(XTX1B-SATA3_TX--Pad154)") (class "Default")
      (node (ref "XTX1") (pin "154") (pinfunction "SATA3_TX-_154") (pintype "passive"))
    )
    (net (code "211") (name "unconnected-(XTX1B-SATALED#-Pad150)") (class "Default")
      (node (ref "XTX1") (pin "150") (pinfunction "SATALED#_150") (pintype "passive"))
    )
    (net (code "212") (name "unconnected-(XTX1B-SLP_S3#-Pad149)") (class "Default")
      (node (ref "XTX1") (pin "149") (pinfunction "SLP_S3#_149") (pintype "passive"))
    )
    (net (code "213") (name "unconnected-(XTX1B-SLP_S5#-Pad165)") (class "Default")
      (node (ref "XTX1") (pin "165") (pinfunction "SLP_S5#_165") (pintype "passive"))
    )
    (net (code "214") (name "unconnected-(XTX1B-SUS_STAT#-Pad132)") (class "Default")
      (node (ref "XTX1") (pin "132") (pinfunction "SUS_STAT#_132") (pintype "passive"))
    )
    (net (code "215") (name "unconnected-(XTX1B-USBP5-Pad125)") (class "Default")
      (node (ref "XTX1") (pin "125") (pinfunction "USBP5_125") (pintype "passive"))
    )
    (net (code "216") (name "unconnected-(XTX1B-VCC-Pad119)") (class "Default")
      (node (ref "XTX1") (pin "119") (pinfunction "VCC_119") (pintype "passive"))
    )
    (net (code "217") (name "unconnected-(XTX1B-VCC-Pad151)") (class "Default")
      (node (ref "XTX1") (pin "151") (pinfunction "VCC_151") (pintype "passive"))
    )
    (net (code "218") (name "unconnected-(XTX1B-VCC-Pad180)") (class "Default")
      (node (ref "XTX1") (pin "180") (pinfunction "VCC_180") (pintype "passive"))
    )
    (net (code "219") (name "unconnected-(XTX1B-VCC-Pad183)") (class "Default")
      (node (ref "XTX1") (pin "183") (pinfunction "VCC_183") (pintype "passive"))
    )
    (net (code "220") (name "unconnected-(XTX1B-VCC-Pad184)") (class "Default")
      (node (ref "XTX1") (pin "184") (pinfunction "VCC_184") (pintype "passive"))
    )
    (net (code "221") (name "unconnected-(XTX1C-ACK#{slash}DRV-Pad284)") (class "Default")
      (node (ref "XTX1") (pin "284") (pinfunction "ACK#/DRV_284") (pintype "passive"))
    )
    (net (code "222") (name "unconnected-(XTX1C-B-Pad204)") (class "Default")
      (node (ref "XTX1") (pin "204") (pinfunction "B_204") (pintype "passive"))
    )
    (net (code "223") (name "unconnected-(XTX1C-BIASON-Pad245)") (class "Default")
      (node (ref "XTX1") (pin "245") (pinfunction "BIASON_245") (pintype "passive"))
    )
    (net (code "224") (name "unconnected-(XTX1C-BLON#-Pad244)") (class "Default")
      (node (ref "XTX1") (pin "244") (pinfunction "BLON#_244") (pintype "passive"))
    )
    (net (code "225") (name "unconnected-(XTX1C-C-Pad250)") (class "Default")
      (node (ref "XTX1") (pin "250") (pinfunction "C_250") (pintype "passive"))
    )
    (net (code "226") (name "unconnected-(XTX1C-COMP-Pad247)") (class "Default")
      (node (ref "XTX1") (pin "247") (pinfunction "COMP_247") (pintype "passive"))
    )
    (net (code "227") (name "unconnected-(XTX1C-CTS1#-Pad293)") (class "Default")
      (node (ref "XTX1") (pin "293") (pinfunction "CTS1#_293") (pintype "passive"))
    )
    (net (code "228") (name "unconnected-(XTX1C-CTS2#-Pad275)") (class "Default")
      (node (ref "XTX1") (pin "275") (pinfunction "CTS2#_275") (pintype "passive"))
    )
    (net (code "229") (name "unconnected-(XTX1C-DCD2#-Pad271)") (class "Default")
      (node (ref "XTX1") (pin "271") (pinfunction "DCD2#_271") (pintype "passive"))
    )
    (net (code "230") (name "unconnected-(XTX1C-DETECT#-Pad209)") (class "Default")
      (node (ref "XTX1") (pin "209") (pinfunction "DETECT#_209") (pintype "passive"))
    )
    (net (code "231") (name "unconnected-(XTX1C-DIGON-Pad246)") (class "Default")
      (node (ref "XTX1") (pin "246") (pinfunction "DIGON_246") (pintype "passive"))
    )
    (net (code "232") (name "unconnected-(XTX1C-DSR1#-Pad291)") (class "Default")
      (node (ref "XTX1") (pin "291") (pinfunction "DSR1#_291") (pintype "passive"))
    )
    (net (code "233") (name "unconnected-(XTX1C-DTR1#-Pad287)") (class "Default")
      (node (ref "XTX1") (pin "287") (pinfunction "DTR1#_287") (pintype "passive"))
    )
    (net (code "234") (name "unconnected-(XTX1C-DTR2#-Pad269)") (class "Default")
      (node (ref "XTX1") (pin "269") (pinfunction "DTR2#_269") (pintype "passive"))
    )
    (net (code "235") (name "unconnected-(XTX1C-ERR#{slash}HDSEL#-Pad260)") (class "Default")
      (node (ref "XTX1") (pin "260") (pinfunction "ERR#/HDSEL#_260") (pintype "passive"))
    )
    (net (code "236") (name "unconnected-(XTX1C-FPDDC_CLK-Pad243)") (class "Default")
      (node (ref "XTX1") (pin "243") (pinfunction "FPDDC_CLK_243") (pintype "passive"))
    )
    (net (code "237") (name "unconnected-(XTX1C-G-Pad206)") (class "Default")
      (node (ref "XTX1") (pin "206") (pinfunction "G_206") (pintype "passive"))
    )
    (net (code "238") (name "unconnected-(XTX1C-GND-Pad201)") (class "Default")
      (node (ref "XTX1") (pin "201") (pinfunction "GND_201") (pintype "passive"))
    )
    (net (code "239") (name "unconnected-(XTX1C-GND-Pad202)") (class "Default")
      (node (ref "XTX1") (pin "202") (pinfunction "GND_202") (pintype "passive"))
    )
    (net (code "240") (name "unconnected-(XTX1C-GND-Pad215)") (class "Default")
      (node (ref "XTX1") (pin "215") (pinfunction "GND_215") (pintype "passive"))
    )
    (net (code "241") (name "unconnected-(XTX1C-GND-Pad221)") (class "Default")
      (node (ref "XTX1") (pin "221") (pinfunction "GND_221") (pintype "passive"))
    )
    (net (code "242") (name "unconnected-(XTX1C-GND-Pad222)") (class "Default")
      (node (ref "XTX1") (pin "222") (pinfunction "GND_222") (pintype "passive"))
    )
    (net (code "243") (name "unconnected-(XTX1C-GND-Pad227)") (class "Default")
      (node (ref "XTX1") (pin "227") (pinfunction "GND_227") (pintype "passive"))
    )
    (net (code "244") (name "unconnected-(XTX1C-GND-Pad228)") (class "Default")
      (node (ref "XTX1") (pin "228") (pinfunction "GND_228") (pintype "passive"))
    )
    (net (code "245") (name "unconnected-(XTX1C-GND-Pad234)") (class "Default")
      (node (ref "XTX1") (pin "234") (pinfunction "GND_234") (pintype "passive"))
    )
    (net (code "246") (name "unconnected-(XTX1C-GND-Pad254)") (class "Default")
      (node (ref "XTX1") (pin "254") (pinfunction "GND_254") (pintype "passive"))
    )
    (net (code "247") (name "unconnected-(XTX1C-GND-Pad265)") (class "Default")
      (node (ref "XTX1") (pin "265") (pinfunction "GND_265") (pintype "passive"))
    )
    (net (code "248") (name "unconnected-(XTX1C-GND-Pad266)") (class "Default")
      (node (ref "XTX1") (pin "266") (pinfunction "GND_266") (pintype "passive"))
    )
    (net (code "249") (name "unconnected-(XTX1C-GND-Pad299)") (class "Default")
      (node (ref "XTX1") (pin "299") (pinfunction "GND_299") (pintype "passive"))
    )
    (net (code "250") (name "unconnected-(XTX1C-GND-Pad300)") (class "Default")
      (node (ref "XTX1") (pin "300") (pinfunction "GND_300") (pintype "passive"))
    )
    (net (code "251") (name "unconnected-(XTX1C-HSY-Pad205)") (class "Default")
      (node (ref "XTX1") (pin "205") (pinfunction "HSY_205") (pintype "passive"))
    )
    (net (code "252") (name "unconnected-(XTX1C-IRRX-Pad259)") (class "Default")
      (node (ref "XTX1") (pin "259") (pinfunction "IRRX_259") (pintype "passive"))
    )
    (net (code "253") (name "unconnected-(XTX1C-IRTX-Pad261)") (class "Default")
      (node (ref "XTX1") (pin "261") (pinfunction "IRTX_261") (pintype "passive"))
    )
    (net (code "254") (name "unconnected-(XTX1C-KBCLK-Pad296)") (class "Default")
      (node (ref "XTX1") (pin "296") (pinfunction "KBCLK_296") (pintype "passive"))
    )
    (net (code "255") (name "unconnected-(XTX1C-KBDAT-Pad298)") (class "Default")
      (node (ref "XTX1") (pin "298") (pinfunction "KBDAT_298") (pintype "passive"))
    )
    (net (code "256") (name "unconnected-(XTX1C-LCDDO0-Pad237)") (class "Default")
      (node (ref "XTX1") (pin "237") (pinfunction "LCDDO0_237") (pintype "passive"))
    )
    (net (code "257") (name "unconnected-(XTX1C-LCDDO2-Pad238)") (class "Default")
      (node (ref "XTX1") (pin "238") (pinfunction "LCDDO2_238") (pintype "passive"))
    )
    (net (code "258") (name "unconnected-(XTX1C-LCDDO3-Pad236)") (class "Default")
      (node (ref "XTX1") (pin "236") (pinfunction "LCDDO3_236") (pintype "passive"))
    )
    (net (code "259") (name "unconnected-(XTX1C-LCDDO4-Pad229)") (class "Default")
      (node (ref "XTX1") (pin "229") (pinfunction "LCDDO4_229") (pintype "passive"))
    )
    (net (code "260") (name "unconnected-(XTX1C-LCDDO7-Pad230)") (class "Default")
      (node (ref "XTX1") (pin "230") (pinfunction "LCDDO7_230") (pintype "passive"))
    )
    (net (code "261") (name "unconnected-(XTX1C-LCDDO8-Pad223)") (class "Default")
      (node (ref "XTX1") (pin "223") (pinfunction "LCDDO8_223") (pintype "passive"))
    )
    (net (code "262") (name "unconnected-(XTX1C-LCDDO11-Pad224)") (class "Default")
      (node (ref "XTX1") (pin "224") (pinfunction "LCDDO11_224") (pintype "passive"))
    )
    (net (code "263") (name "unconnected-(XTX1C-LCDDO13-Pad217)") (class "Default")
      (node (ref "XTX1") (pin "217") (pinfunction "LCDDO13_217") (pintype "passive"))
    )
    (net (code "264") (name "unconnected-(XTX1C-LCDDO16-Pad211)") (class "Default")
      (node (ref "XTX1") (pin "211") (pinfunction "LCDDO16_211") (pintype "passive"))
    )
    (net (code "265") (name "unconnected-(XTX1C-MSCLK-Pad292)") (class "Default")
      (node (ref "XTX1") (pin "292") (pinfunction "MSCLK_292") (pintype "passive"))
    )
    (net (code "266") (name "unconnected-(XTX1C-MSDAT-Pad294)") (class "Default")
      (node (ref "XTX1") (pin "294") (pinfunction "MSDAT_294") (pintype "passive"))
    )
    (net (code "267") (name "unconnected-(XTX1C-PD1{slash}TRK0#-Pad278)") (class "Default")
      (node (ref "XTX1") (pin "278") (pinfunction "PD1/TRK0#_278") (pintype "passive"))
    )
    (net (code "268") (name "unconnected-(XTX1C-PD2{slash}WP#-Pad276)") (class "Default")
      (node (ref "XTX1") (pin "276") (pinfunction "PD2/WP#_276") (pintype "passive"))
    )
    (net (code "269") (name "unconnected-(XTX1C-PD4{slash}DSKCHG#-Pad272)") (class "Default")
      (node (ref "XTX1") (pin "272") (pinfunction "PD4/DSKCHG#_272") (pintype "passive"))
    )
    (net (code "270") (name "unconnected-(XTX1C-PD5{slash}RESERVED-Pad268)") (class "Default")
      (node (ref "XTX1") (pin "268") (pinfunction "PD5/RESERVED_268") (pintype "passive"))
    )
    (net (code "271") (name "unconnected-(XTX1C-PD6{slash}RESERVED-Pad262)") (class "Default")
      (node (ref "XTX1") (pin "262") (pinfunction "PD6/RESERVED_262") (pintype "passive"))
    )
    (net (code "272") (name "unconnected-(XTX1C-PE{slash}WDATA#-Pad288)") (class "Default")
      (node (ref "XTX1") (pin "288") (pinfunction "PE/WDATA#_288") (pintype "passive"))
    )
    (net (code "273") (name "unconnected-(XTX1C-R-Pad203)") (class "Default")
      (node (ref "XTX1") (pin "203") (pinfunction "R_203") (pintype "passive"))
    )
    (net (code "274") (name "unconnected-(XTX1C-RESERVED-Pad252)") (class "Default")
      (node (ref "XTX1") (pin "252") (pinfunction "RESERVED_252") (pintype "passive"))
    )
    (net (code "275") (name "unconnected-(XTX1C-RI1#-Pad297)") (class "Default")
      (node (ref "XTX1") (pin "297") (pinfunction "RI1#_297") (pintype "passive"))
    )
    (net (code "276") (name "unconnected-(XTX1C-RTS1#-Pad285)") (class "Default")
      (node (ref "XTX1") (pin "285") (pinfunction "RTS1#_285") (pintype "passive"))
    )
    (net (code "277") (name "unconnected-(XTX1C-RTS2#-Pad267)") (class "Default")
      (node (ref "XTX1") (pin "267") (pinfunction "RTS2#_267") (pintype "passive"))
    )
    (net (code "278") (name "unconnected-(XTX1C-RXD1-Pad283)") (class "Default")
      (node (ref "XTX1") (pin "283") (pinfunction "RXD1_283") (pintype "passive"))
    )
    (net (code "279") (name "unconnected-(XTX1C-SLIN#{slash}STEP#-Pad270)") (class "Default")
      (node (ref "XTX1") (pin "270") (pinfunction "SLIN#/STEP#_270") (pintype "passive"))
    )
    (net (code "280") (name "unconnected-(XTX1C-STB#{slash}RESERVED-Pad255)") (class "Default")
      (node (ref "XTX1") (pin "255") (pinfunction "STB#/RESERVED_255") (pintype "passive"))
    )
    (net (code "281") (name "unconnected-(XTX1C-SYNC-Pad249)") (class "Default")
      (node (ref "XTX1") (pin "249") (pinfunction "SYNC_249") (pintype "passive"))
    )
    (net (code "282") (name "unconnected-(XTX1C-TXD1-Pad295)") (class "Default")
      (node (ref "XTX1") (pin "295") (pinfunction "TXD1_295") (pintype "passive"))
    )
    (net (code "283") (name "unconnected-(XTX1C-TXD2-Pad277)") (class "Default")
      (node (ref "XTX1") (pin "277") (pinfunction "TXD2_277") (pintype "passive"))
    )
    (net (code "284") (name "unconnected-(XTX1C-VCC-Pad239)") (class "Default")
      (node (ref "XTX1") (pin "239") (pinfunction "VCC_239") (pintype "passive"))
    )
    (net (code "285") (name "unconnected-(XTX1C-VCC-Pad240)") (class "Default")
      (node (ref "XTX1") (pin "240") (pinfunction "VCC_240") (pintype "passive"))
    )
    (net (code "286") (name "unconnected-(XTX1C-VCC-Pad281)") (class "Default")
      (node (ref "XTX1") (pin "281") (pinfunction "VCC_281") (pintype "passive"))
    )
    (net (code "287") (name "unconnected-(XTX1C-VCC-Pad282)") (class "Default")
      (node (ref "XTX1") (pin "282") (pinfunction "VCC_282") (pintype "passive"))
    )
    (net (code "288") (name "unconnected-(XTX1D-BATLOW#-Pad341)") (class "Default")
      (node (ref "XTX1") (pin "341") (pinfunction "BATLOW#_341") (pintype "passive"))
    )
    (net (code "289") (name "unconnected-(XTX1D-CBLID_P#-Pad390)") (class "Default")
      (node (ref "XTX1") (pin "390") (pinfunction "CBLID_P#_390") (pintype "passive"))
    )
    (net (code "290") (name "unconnected-(XTX1D-DASP_S-Pad328)") (class "Default")
      (node (ref "XTX1") (pin "328") (pinfunction "DASP_S_328") (pintype "passive"))
    )
    (net (code "291") (name "unconnected-(XTX1D-EXTSMI#-Pad321)") (class "Default")
      (node (ref "XTX1") (pin "321") (pinfunction "EXTSMI#_321") (pintype "passive"))
    )
    (net (code "292") (name "unconnected-(XTX1D-EXT_PRG-Pad315)") (class "Default")
      (node (ref "XTX1") (pin "315") (pinfunction "EXT_PRG_315") (pintype "passive"))
    )
    (net (code "293") (name "unconnected-(XTX1D-GPCS#-Pad320)") (class "Default")
      (node (ref "XTX1") (pin "320") (pinfunction "GPCS#_320") (pintype "passive"))
    )
    (net (code "294") (name "unconnected-(XTX1D-GPE1#-Pad342)") (class "Default")
      (node (ref "XTX1") (pin "342") (pinfunction "GPE1#_342") (pintype "passive"))
    )
    (net (code "295") (name "unconnected-(XTX1D-GPE2#-Pad389)") (class "Default")
      (node (ref "XTX1") (pin "389") (pinfunction "GPE2#_389") (pintype "passive"))
    )
    (net (code "296") (name "unconnected-(XTX1D-HDRST#-Pad398)") (class "Default")
      (node (ref "XTX1") (pin "398") (pinfunction "HDRST#_398") (pintype "passive"))
    )
    (net (code "297") (name "unconnected-(XTX1D-KBINH#-Pad309)") (class "Default")
      (node (ref "XTX1") (pin "309") (pinfunction "KBINH#_309") (pintype "passive"))
    )
    (net (code "298") (name "unconnected-(XTX1D-PDIAG_S-Pad335)") (class "Default")
      (node (ref "XTX1") (pin "335") (pinfunction "PDIAG_S_335") (pintype "passive"))
    )
    (net (code "299") (name "unconnected-(XTX1D-PIDE_A0-Pad338)") (class "Default")
      (node (ref "XTX1") (pin "338") (pinfunction "PIDE_A0_338") (pintype "passive"))
    )
    (net (code "300") (name "unconnected-(XTX1D-PIDE_A1-Pad340)") (class "Default")
      (node (ref "XTX1") (pin "340") (pinfunction "PIDE_A1_340") (pintype "passive"))
    )
    (net (code "301") (name "unconnected-(XTX1D-PIDE_A2-Pad336)") (class "Default")
      (node (ref "XTX1") (pin "336") (pinfunction "PIDE_A2_336") (pintype "passive"))
    )
    (net (code "302") (name "unconnected-(XTX1D-PIDE_AK#-Pad346)") (class "Default")
      (node (ref "XTX1") (pin "346") (pinfunction "PIDE_AK#_346") (pintype "passive"))
    )
    (net (code "303") (name "unconnected-(XTX1D-PIDE_CS1#-Pad332)") (class "Default")
      (node (ref "XTX1") (pin "332") (pinfunction "PIDE_CS1#_332") (pintype "passive"))
    )
    (net (code "304") (name "unconnected-(XTX1D-PIDE_CS3#-Pad330)") (class "Default")
      (node (ref "XTX1") (pin "330") (pinfunction "PIDE_CS3#_330") (pintype "passive"))
    )
    (net (code "305") (name "unconnected-(XTX1D-PIDE_D0-Pad360)") (class "Default")
      (node (ref "XTX1") (pin "360") (pinfunction "PIDE_D0_360") (pintype "passive"))
    )
    (net (code "306") (name "unconnected-(XTX1D-PIDE_D1-Pad364)") (class "Default")
      (node (ref "XTX1") (pin "364") (pinfunction "PIDE_D1_364") (pintype "passive"))
    )
    (net (code "307") (name "unconnected-(XTX1D-PIDE_D2-Pad370)") (class "Default")
      (node (ref "XTX1") (pin "370") (pinfunction "PIDE_D2_370") (pintype "passive"))
    )
    (net (code "308") (name "unconnected-(XTX1D-PIDE_D3-Pad374)") (class "Default")
      (node (ref "XTX1") (pin "374") (pinfunction "PIDE_D3_374") (pintype "passive"))
    )
    (net (code "309") (name "unconnected-(XTX1D-PIDE_D4-Pad378)") (class "Default")
      (node (ref "XTX1") (pin "378") (pinfunction "PIDE_D4_378") (pintype "passive"))
    )
    (net (code "310") (name "unconnected-(XTX1D-PIDE_D5-Pad384)") (class "Default")
      (node (ref "XTX1") (pin "384") (pinfunction "PIDE_D5_384") (pintype "passive"))
    )
    (net (code "311") (name "unconnected-(XTX1D-PIDE_D6-Pad388)") (class "Default")
      (node (ref "XTX1") (pin "388") (pinfunction "PIDE_D6_388") (pintype "passive"))
    )
    (net (code "312") (name "unconnected-(XTX1D-PIDE_D7-Pad396)") (class "Default")
      (node (ref "XTX1") (pin "396") (pinfunction "PIDE_D7_396") (pintype "passive"))
    )
    (net (code "313") (name "unconnected-(XTX1D-PIDE_D8-Pad392)") (class "Default")
      (node (ref "XTX1") (pin "392") (pinfunction "PIDE_D8_392") (pintype "passive"))
    )
    (net (code "314") (name "unconnected-(XTX1D-PIDE_D9-Pad386)") (class "Default")
      (node (ref "XTX1") (pin "386") (pinfunction "PIDE_D9_386") (pintype "passive"))
    )
    (net (code "315") (name "unconnected-(XTX1D-PIDE_D10-Pad380)") (class "Default")
      (node (ref "XTX1") (pin "380") (pinfunction "PIDE_D10_380") (pintype "passive"))
    )
    (net (code "316") (name "unconnected-(XTX1D-PIDE_D11-Pad376)") (class "Default")
      (node (ref "XTX1") (pin "376") (pinfunction "PIDE_D11_376") (pintype "passive"))
    )
    (net (code "317") (name "unconnected-(XTX1D-PIDE_D12-Pad372)") (class "Default")
      (node (ref "XTX1") (pin "372") (pinfunction "PIDE_D12_372") (pintype "passive"))
    )
    (net (code "318") (name "unconnected-(XTX1D-PIDE_D13-Pad368)") (class "Default")
      (node (ref "XTX1") (pin "368") (pinfunction "PIDE_D13_368") (pintype "passive"))
    )
    (net (code "319") (name "unconnected-(XTX1D-PIDE_D14-Pad362)") (class "Default")
      (node (ref "XTX1") (pin "362") (pinfunction "PIDE_D14_362") (pintype "passive"))
    )
    (net (code "320") (name "unconnected-(XTX1D-PIDE_D15-Pad358)") (class "Default")
      (node (ref "XTX1") (pin "358") (pinfunction "PIDE_D15_358") (pintype "passive"))
    )
    (net (code "321") (name "unconnected-(XTX1D-PIDE_DRQ-Pad356)") (class "Default")
      (node (ref "XTX1") (pin "356") (pinfunction "PIDE_DRQ_356") (pintype "passive"))
    )
    (net (code "322") (name "unconnected-(XTX1D-PIDE_INTRQ-Pad344)") (class "Default")
      (node (ref "XTX1") (pin "344") (pinfunction "PIDE_INTRQ_344") (pintype "passive"))
    )
    (net (code "323") (name "unconnected-(XTX1D-PIDE_IOR#-Pad352)") (class "Default")
      (node (ref "XTX1") (pin "352") (pinfunction "PIDE_IOR#_352") (pintype "passive"))
    )
    (net (code "324") (name "unconnected-(XTX1D-PIDE_IOW#-Pad354)") (class "Default")
      (node (ref "XTX1") (pin "354") (pinfunction "PIDE_IOW#_354") (pintype "passive"))
    )
    (net (code "325") (name "unconnected-(XTX1D-PIDE_RDY-Pad348)") (class "Default")
      (node (ref "XTX1") (pin "348") (pinfunction "PIDE_RDY_348") (pintype "passive"))
    )
    (net (code "326") (name "unconnected-(XTX1D-PS_ON#-Pad305)") (class "Default")
      (node (ref "XTX1") (pin "305") (pinfunction "PS_ON#_305") (pintype "passive"))
    )
    (net (code "327") (name "unconnected-(XTX1D-ROMKBCS#-Pad313)") (class "Default")
      (node (ref "XTX1") (pin "313") (pinfunction "ROMKBCS#_313") (pintype "passive"))
    )
    (net (code "328") (name "unconnected-(XTX1D-RSMRST#-Pad311)") (class "Default")
      (node (ref "XTX1") (pin "311") (pinfunction "RSMRST#_311") (pintype "passive"))
    )
    (net (code "329") (name "unconnected-(XTX1D-SIDE_A0-Pad331)") (class "Default")
      (node (ref "XTX1") (pin "331") (pinfunction "SIDE_A0_331") (pintype "passive"))
    )
    (net (code "330") (name "unconnected-(XTX1D-SIDE_A1-Pad337)") (class "Default")
      (node (ref "XTX1") (pin "337") (pinfunction "SIDE_A1_337") (pintype "passive"))
    )
    (net (code "331") (name "unconnected-(XTX1D-SIDE_A2-Pad329)") (class "Default")
      (node (ref "XTX1") (pin "329") (pinfunction "SIDE_A2_329") (pintype "passive"))
    )
    (net (code "332") (name "unconnected-(XTX1D-SIDE_AK#-Pad343)") (class "Default")
      (node (ref "XTX1") (pin "343") (pinfunction "SIDE_AK#_343") (pintype "passive"))
    )
    (net (code "333") (name "unconnected-(XTX1D-SIDE_CS1#-Pad327)") (class "Default")
      (node (ref "XTX1") (pin "327") (pinfunction "SIDE_CS1#_327") (pintype "passive"))
    )
    (net (code "334") (name "unconnected-(XTX1D-SIDE_CS3#-Pad325)") (class "Default")
      (node (ref "XTX1") (pin "325") (pinfunction "SIDE_CS3#_325") (pintype "passive"))
    )
    (net (code "335") (name "unconnected-(XTX1D-SIDE_D0-Pad357)") (class "Default")
      (node (ref "XTX1") (pin "357") (pinfunction "SIDE_D0_357") (pintype "passive"))
    )
    (net (code "336") (name "unconnected-(XTX1D-SIDE_D1-Pad361)") (class "Default")
      (node (ref "XTX1") (pin "361") (pinfunction "SIDE_D1_361") (pintype "passive"))
    )
    (net (code "337") (name "unconnected-(XTX1D-SIDE_D2-Pad367)") (class "Default")
      (node (ref "XTX1") (pin "367") (pinfunction "SIDE_D2_367") (pintype "passive"))
    )
    (net (code "338") (name "unconnected-(XTX1D-SIDE_D3-Pad371)") (class "Default")
      (node (ref "XTX1") (pin "371") (pinfunction "SIDE_D3_371") (pintype "passive"))
    )
    (net (code "339") (name "unconnected-(XTX1D-SIDE_D4-Pad375)") (class "Default")
      (node (ref "XTX1") (pin "375") (pinfunction "SIDE_D4_375") (pintype "passive"))
    )
    (net (code "340") (name "unconnected-(XTX1D-SIDE_D5-Pad379)") (class "Default")
      (node (ref "XTX1") (pin "379") (pinfunction "SIDE_D5_379") (pintype "passive"))
    )
    (net (code "341") (name "unconnected-(XTX1D-SIDE_D6-Pad385)") (class "Default")
      (node (ref "XTX1") (pin "385") (pinfunction "SIDE_D6_385") (pintype "passive"))
    )
    (net (code "342") (name "unconnected-(XTX1D-SIDE_D7-Pad394)") (class "Default")
      (node (ref "XTX1") (pin "394") (pinfunction "SIDE_D7_394") (pintype "passive"))
    )
    (net (code "343") (name "unconnected-(XTX1D-SIDE_D8-Pad387)") (class "Default")
      (node (ref "XTX1") (pin "387") (pinfunction "SIDE_D8_387") (pintype "passive"))
    )
    (net (code "344") (name "unconnected-(XTX1D-SIDE_D9-Pad383)") (class "Default")
      (node (ref "XTX1") (pin "383") (pinfunction "SIDE_D9_383") (pintype "passive"))
    )
    (net (code "345") (name "unconnected-(XTX1D-SIDE_D10-Pad377)") (class "Default")
      (node (ref "XTX1") (pin "377") (pinfunction "SIDE_D10_377") (pintype "passive"))
    )
    (net (code "346") (name "unconnected-(XTX1D-SIDE_D11-Pad373)") (class "Default")
      (node (ref "XTX1") (pin "373") (pinfunction "SIDE_D11_373") (pintype "passive"))
    )
    (net (code "347") (name "unconnected-(XTX1D-SIDE_D12-Pad369)") (class "Default")
      (node (ref "XTX1") (pin "369") (pinfunction "SIDE_D12_369") (pintype "passive"))
    )
    (net (code "348") (name "unconnected-(XTX1D-SIDE_D13-Pad363)") (class "Default")
      (node (ref "XTX1") (pin "363") (pinfunction "SIDE_D13_363") (pintype "passive"))
    )
    (net (code "349") (name "unconnected-(XTX1D-SIDE_D14-Pad359)") (class "Default")
      (node (ref "XTX1") (pin "359") (pinfunction "SIDE_D14_359") (pintype "passive"))
    )
    (net (code "350") (name "unconnected-(XTX1D-SIDE_D15-Pad355)") (class "Default")
      (node (ref "XTX1") (pin "355") (pinfunction "SIDE_D15_355") (pintype "passive"))
    )
    (net (code "351") (name "unconnected-(XTX1D-SIDE_DRQ-Pad353)") (class "Default")
      (node (ref "XTX1") (pin "353") (pinfunction "SIDE_DRQ_353") (pintype "passive"))
    )
    (net (code "352") (name "unconnected-(XTX1D-SIDE_INTRQ-Pad339)") (class "Default")
      (node (ref "XTX1") (pin "339") (pinfunction "SIDE_INTRQ_339") (pintype "passive"))
    )
    (net (code "353") (name "unconnected-(XTX1D-SIDE_IOR#-Pad347)") (class "Default")
      (node (ref "XTX1") (pin "347") (pinfunction "SIDE_IOR#_347") (pintype "passive"))
    )
    (net (code "354") (name "unconnected-(XTX1D-SIDE_IOW#-Pad351)") (class "Default")
      (node (ref "XTX1") (pin "351") (pinfunction "SIDE_IOW#_351") (pintype "passive"))
    )
    (net (code "355") (name "unconnected-(XTX1D-SIDE_RDY-Pad345)") (class "Default")
      (node (ref "XTX1") (pin "345") (pinfunction "SIDE_RDY_345") (pintype "passive"))
    )
    (net (code "356") (name "unconnected-(XTX1D-SMBALRT#-Pad326)") (class "Default")
      (node (ref "XTX1") (pin "326") (pinfunction "SMBALRT#_326") (pintype "passive"))
    )
    (net (code "357") (name "unconnected-(XTX1D-SMBCLK-Pad323)") (class "Default")
      (node (ref "XTX1") (pin "323") (pinfunction "SMBCLK_323") (pintype "passive"))
    )
    (net (code "358") (name "unconnected-(XTX1D-SMBDATA-Pad324)") (class "Default")
      (node (ref "XTX1") (pin "324") (pinfunction "SMBDATA_324") (pintype "passive"))
    )
    (net (code "359") (name "unconnected-(XTX1D-SPEAKER-Pad306)") (class "Default")
      (node (ref "XTX1") (pin "306") (pinfunction "SPEAKER_306") (pintype "passive"))
    )
  )
)
